# transmitter.net
KiCad netlist of a schematic drawn in Altium Designer
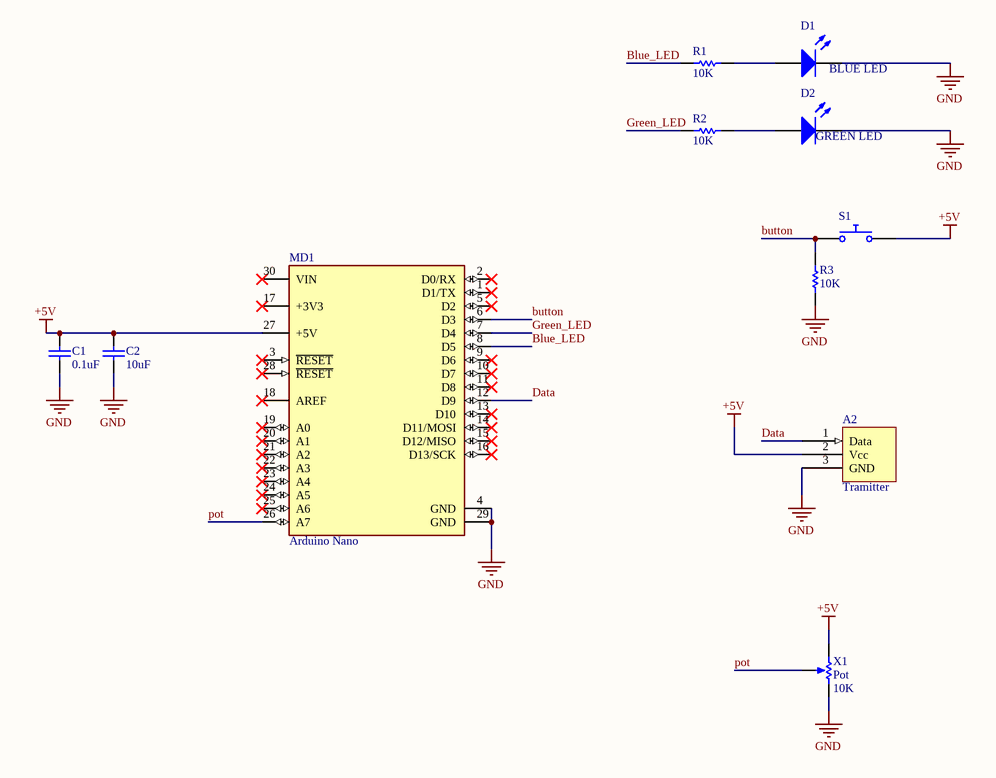
[diagram p0: transmitter.SchDoc]

(export (version "E")
  (design (tool "Eeschema 10.0.6"))
  (components
    (comp (ref "A2")
      (value "Tramitter")
      (description "433MHz RF Transmitter Module")
      (libsource (lib "Circuits") (part "Transmitter"))
    )
    (comp (ref "C1")
      (value "0.1uF")
      (description "Capacitor")
      (libsource (lib "Simulation Generic Components") (part "Capacitor"))
    )
    (comp (ref "C2")
      (value "10uF")
      (description "Capacitor")
      (libsource (lib "Simulation Generic Components") (part "Capacitor"))
    )
    (comp (ref "D1")
      (value "BLUE LED")
      (description "Light-Emitting Diode")
      (libsource (lib "Simulation Generic Components") (part "LED"))
    )
    (comp (ref "D2")
      (value "GREEN LED")
      (description "Light-Emitting Diode")
      (libsource (lib "Simulation Generic Components") (part "LED"))
    )
    (comp (ref "MD1")
      (value "Arduino Nano")
      (footprint "FP-A000005-MFG")
      (description "ARDUINO NANO ATMEGA328 EVAL BRD")
      (libsource (lib "Altium Content Vault") (part "d190c066e99afd1c6882cf92e11b2cc"))
    )
    (comp (ref "R1")
      (value "10K")
      (description "Resistor")
      (libsource (lib "Simulation Generic Components") (part "Resistor"))
    )
    (comp (ref "R2")
      (value "10K")
      (description "Resistor")
      (libsource (lib "Simulation Generic Components") (part "Resistor"))
    )
    (comp (ref "R3")
      (value "10K")
      (description "Resistor")
      (libsource (lib "Simulation Generic Components") (part "Resistor"))
    )
    (comp (ref "S1")
      (value "Push Button Normally Opened")
      (libsource (lib "Simulation Generic Components") (part "Push Button NO"))
    )
    (comp (ref "X1")
      (value "Pot")
      (description "Potentiometer")
      (fields (field (name "ALTIUM_VALUE") "10K"))
      (libsource (lib "Simulation Generic Components") (part "Potentiometer"))
    )
  )
  (nets
    (net (code "1") (name "+5V") (class "Default")
      (node (ref "A2") (pin "2") (pinfunction "Vcc_2") (pintype "power_in"))
      (node (ref "C1") (pin "2") (pinfunction "2_2") (pintype "passive"))
      (node (ref "C2") (pin "2") (pinfunction "2_2") (pintype "passive"))
      (node (ref "MD1") (pin "27") (pinfunction "+5V_27") (pintype "power_in"))
      (node (ref "S1") (pin "2") (pinfunction "2_2") (pintype "passive"))
      (node (ref "X1") (pin "1") (pinfunction "TOP_1") (pintype "passive"))
    )
    (net (code "2") (name "/Blue_LED") (class "Default")
      (node (ref "MD1") (pin "8") (pinfunction "D5_8") (pintype "bidirectional"))
      (node (ref "R1") (pin "1") (pinfunction "1_1") (pintype "passive"))
    )
    (net (code "3") (name "/Data") (class "Default")
      (node (ref "A2") (pin "1") (pinfunction "Data_1") (pintype "input"))
      (node (ref "MD1") (pin "12") (pinfunction "D9_12") (pintype "bidirectional"))
    )
    (net (code "4") (name "/Green_LED") (class "Default")
      (node (ref "MD1") (pin "7") (pinfunction "D4_7") (pintype "bidirectional"))
      (node (ref "R2") (pin "1") (pinfunction "1_1") (pintype "passive"))
    )
    (net (code "5") (name "/button") (class "Default")
      (node (ref "MD1") (pin "6") (pinfunction "D3_6") (pintype "bidirectional"))
      (node (ref "R3") (pin "2") (pinfunction "2_2") (pintype "passive"))
      (node (ref "S1") (pin "1") (pinfunction "1_1") (pintype "passive"))
    )
    (net (code "6") (name "/pot") (class "Default")
      (node (ref "MD1") (pin "26") (pinfunction "A7_26") (pintype "bidirectional"))
      (node (ref "X1") (pin "3") (pinfunction "TAP_3") (pintype "passive"))
    )
    (net (code "7") (name "GND") (class "Default")
      (node (ref "A2") (pin "3") (pinfunction "GND_3") (pintype "power_in"))
      (node (ref "C1") (pin "1") (pinfunction "1_1") (pintype "passive"))
      (node (ref "C2") (pin "1") (pinfunction "1_1") (pintype "passive"))
      (node (ref "D1") (pin "2") (pinfunction "K_2") (pintype "passive"))
      (node (ref "D2") (pin "2") (pinfunction "K_2") (pintype "passive"))
      (node (ref "MD1") (pin "29") (pinfunction "GND_29") (pintype "power_in"))
      (node (ref "MD1") (pin "4") (pinfunction "GND_4") (pintype "power_in"))
      (node (ref "R3") (pin "1") (pinfunction "1_1") (pintype "passive"))
      (node (ref "X1") (pin "2") (pinfunction "BOT_2") (pintype "passive"))
    )
    (net (code "8") (name "Net-(D1-A)") (class "Default")
      (node (ref "D1") (pin "1") (pinfunction "A_1") (pintype "passive"))
      (node (ref "R1") (pin "2") (pinfunction "2_2") (pintype "passive"))
    )
    (net (code "9") (name "Net-(D2-A)") (class "Default")
      (node (ref "D2") (pin "1") (pinfunction "A_1") (pintype "passive"))
      (node (ref "R2") (pin "2") (pinfunction "2_2") (pintype "passive"))
    )
    (net (code "10") (name "unconnected-(MD1-+3V3-Pad17)") (class "Default")
      (node (ref "MD1") (pin "17") (pinfunction "+3V3_17") (pintype "power_in+no_connect"))
    )
    (net (code "11") (name "unconnected-(MD1-A0-Pad19)") (class "Default")
      (node (ref "MD1") (pin "19") (pinfunction "A0_19") (pintype "bidirectional+no_connect"))
    )
    (net (code "12") (name "unconnected-(MD1-A1-Pad20)") (class "Default")
      (node (ref "MD1") (pin "20") (pinfunction "A1_20") (pintype "bidirectional+no_connect"))
    )
    (net (code "13") (name "unconnected-(MD1-A2-Pad21)") (class "Default")
      (node (ref "MD1") (pin "21") (pinfunction "A2_21") (pintype "bidirectional+no_connect"))
    )
    (net (code "14") (name "unconnected-(MD1-A3-Pad22)") (class "Default")
      (node (ref "MD1") (pin "22") (pinfunction "A3_22") (pintype "bidirectional+no_connect"))
    )
    (net (code "15") (name "unconnected-(MD1-A4-Pad23)") (class "Default")
      (node (ref "MD1") (pin "23") (pinfunction "A4_23") (pintype "bidirectional+no_connect"))
    )
    (net (code "16") (name "unconnected-(MD1-A5-Pad24)") (class "Default")
      (node (ref "MD1") (pin "24") (pinfunction "A5_24") (pintype "bidirectional+no_connect"))
    )
    (net (code "17") (name "unconnected-(MD1-A6-Pad25)") (class "Default")
      (node (ref "MD1") (pin "25") (pinfunction "A6_25") (pintype "bidirectional+no_connect"))
    )
    (net (code "18") (name "unconnected-(MD1-AREF-Pad18)") (class "Default")
      (node (ref "MD1") (pin "18") (pinfunction "AREF_18") (pintype "passive+no_connect"))
    )
    (net (code "19") (name "unconnected-(MD1-D0{slash}RX-Pad2)") (class "Default")
      (node (ref "MD1") (pin "2") (pinfunction "D0/RX_2") (pintype "bidirectional+no_connect"))
    )
    (net (code "20") (name "unconnected-(MD1-D1{slash}TX-Pad1)") (class "Default")
      (node (ref "MD1") (pin "1") (pinfunction "D1/TX_1") (pintype "bidirectional+no_connect"))
    )
    (net (code "21") (name "unconnected-(MD1-D2-Pad5)") (class "Default")
      (node (ref "MD1") (pin "5") (pinfunction "D2_5") (pintype "bidirectional+no_connect"))
    )
    (net (code "22") (name "unconnected-(MD1-D6-Pad9)") (class "Default")
      (node (ref "MD1") (pin "9") (pinfunction "D6_9") (pintype "bidirectional+no_connect"))
    )
    (net (code "23") (name "unconnected-(MD1-D7-Pad10)") (class "Default")
      (node (ref "MD1") (pin "10") (pinfunction "D7_10") (pintype "bidirectional+no_connect"))
    )
    (net (code "24") (name "unconnected-(MD1-D8-Pad11)") (class "Default")
      (node (ref "MD1") (pin "11") (pinfunction "D8_11") (pintype "bidirectional+no_connect"))
    )
    (net (code "25") (name "unconnected-(MD1-D10-Pad13)") (class "Default")
      (node (ref "MD1") (pin "13") (pinfunction "D10_13") (pintype "bidirectional+no_connect"))
    )
    (net (code "26") (name "unconnected-(MD1-D11{slash}MOSI-Pad14)") (class "Default")
      (node (ref "MD1") (pin "14") (pinfunction "D11/MOSI_14") (pintype "bidirectional+no_connect"))
    )
    (net (code "27") (name "unconnected-(MD1-D12{slash}MISO-Pad15)") (class "Default")
      (node (ref "MD1") (pin "15") (pinfunction "D12/MISO_15") (pintype "bidirectional+no_connect"))
    )
    (net (code "28") (name "unconnected-(MD1-D13{slash}SCK-Pad16)") (class "Default")
      (node (ref "MD1") (pin "16") (pinfunction "D13/SCK_16") (pintype "bidirectional+no_connect"))
    )
    (net (code "29") (name "unconnected-(MD1-VIN-Pad30)") (class "Default")
      (node (ref "MD1") (pin "30") (pinfunction "VIN_30") (pintype "power_in+no_connect"))
    )
    (net (code "30") (name "unconnected-(MD1-~{RESET}-Pad3)") (class "Default")
      (node (ref "MD1") (pin "3") (pinfunction "~{RESET}_3") (pintype "input+no_connect"))
    )
    (net (code "31") (name "unconnected-(MD1-~{RESET}-Pad28)") (class "Default")
      (node (ref "MD1") (pin "28") (pinfunction "~{RESET}_28") (pintype "input+no_connect"))
    )
  )
)
